# Powerboard.net
KiCad netlist of a schematic drawn in EAGLE
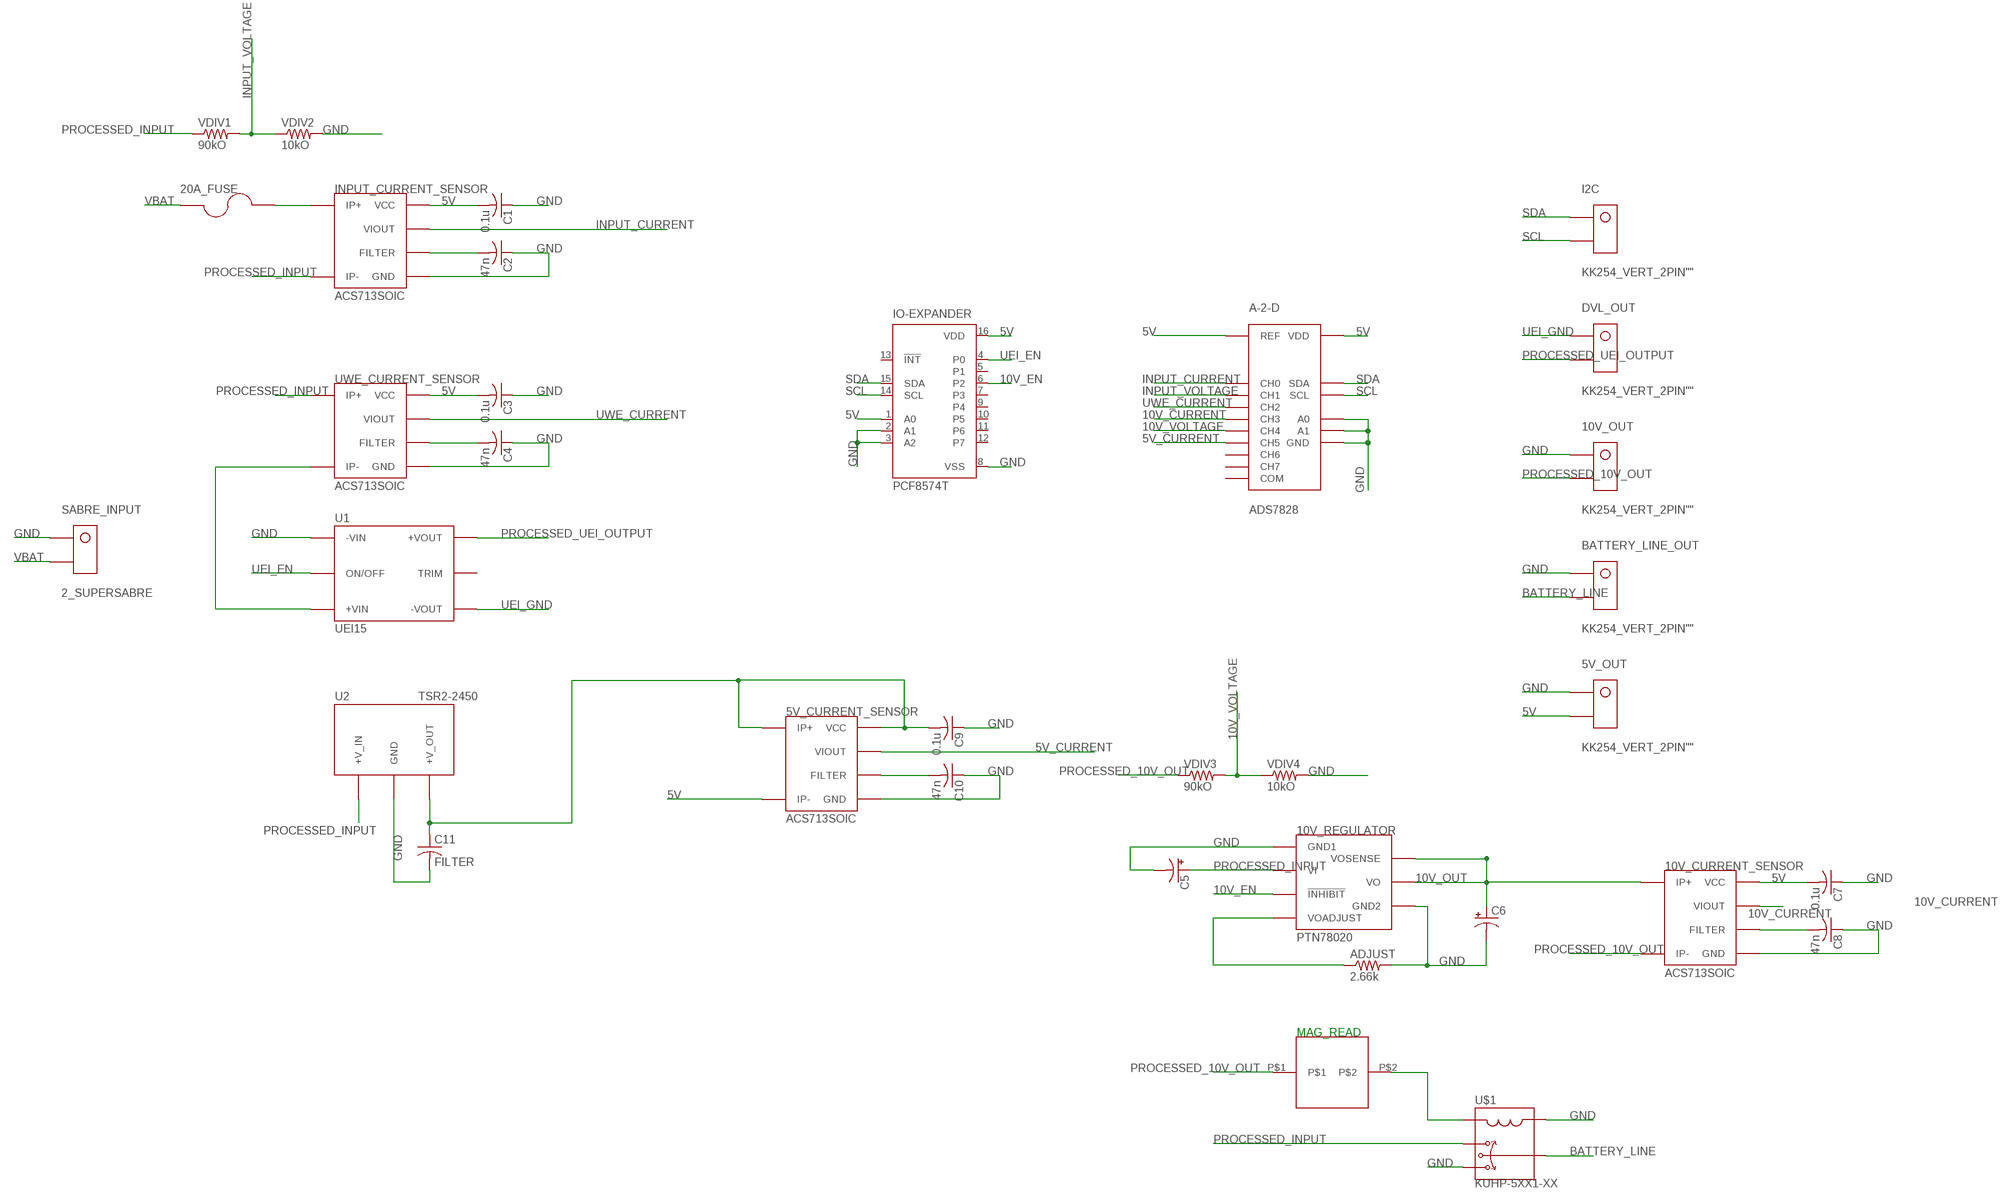
[diagram p0: schematic, sheet 1]

(export (version "E")
  (design (tool "Eeschema 10.0.6"))
  (components
    (comp (ref "5V_CURRENT_SENSOR")
      (value "ACS713SOIC")
      (footprint "eagle-import:ACS713-SOIC")
      (libsource (lib "eagle-import") (part "ACS713SOIC"))
    )
    (comp (ref "5V_OUT")
      (value "KK254_VERT_2PIN\"\"")
      (footprint "eagle-import:KK254_VERT_2PIN")
      (libsource (lib "eagle-import") (part "KK254_VERT_2PIN{dblquote}{dblquote}"))
    )
    (comp (ref "10V_CURRENT_SENSOR")
      (value "ACS713SOIC")
      (footprint "eagle-import:ACS713-SOIC")
      (libsource (lib "eagle-import") (part "ACS713SOIC"))
    )
    (comp (ref "10V_OUT")
      (value "KK254_VERT_2PIN\"\"")
      (footprint "eagle-import:KK254_VERT_2PIN")
      (libsource (lib "eagle-import") (part "KK254_VERT_2PIN{dblquote}{dblquote}"))
    )
    (comp (ref "10V_REGULATOR")
      (value "PTN78020")
      (footprint "eagle-import:PTN")
      (libsource (lib "eagle-import") (part "PTN78020"))
    )
    (comp (ref "20A_FUSE")
      (value "BOWED-1.25\"-FUSECLIPS")
      (footprint "eagle-import:1.25__FUSECLIPS")
      (libsource (lib "eagle-import") (part "BOWED-1.25{dblquote}-FUSECLIPS"))
    )
    (comp (ref "A-2-D")
      (value "ADS7828")
      (footprint "eagle-import:TSSOP16")
      (libsource (lib "eagle-import") (part "ADS7828"))
    )
    (comp (ref "ADJUST")
      (value "2.66k")
      (footprint "eagle-import:R0805")
      (libsource (lib "eagle-import") (part "R-US_R0805"))
    )
    (comp (ref "BATTERY_LINE_OUT")
      (value "KK254_VERT_2PIN\"\"")
      (footprint "eagle-import:KK254_VERT_2PIN")
      (libsource (lib "eagle-import") (part "KK254_VERT_2PIN{dblquote}{dblquote}"))
    )
    (comp (ref "C1")
      (value "0.1u")
      (footprint "eagle-import:C0805")
      (libsource (lib "eagle-import") (part "C-USC0805"))
    )
    (comp (ref "C2")
      (value "47n")
      (footprint "eagle-import:C0805")
      (libsource (lib "eagle-import") (part "C-USC0805"))
    )
    (comp (ref "C3")
      (value "0.1u")
      (footprint "eagle-import:C0805")
      (libsource (lib "eagle-import") (part "C-USC0805"))
    )
    (comp (ref "C4")
      (value "47n")
      (footprint "eagle-import:C0805")
      (libsource (lib "eagle-import") (part "C-USC0805"))
    )
    (comp (ref "C5")
      (value "CPOL-US")
      (footprint "eagle-import:PANASONIC_A_TYPE_M")
      (libsource (lib "eagle-import") (part "CPOL-US"))
    )
    (comp (ref "C6")
      (value "CPOL-US")
      (footprint "eagle-import:PANASONIC_A_TYPE_M")
      (libsource (lib "eagle-import") (part "CPOL-US"))
    )
    (comp (ref "C7")
      (value "0.1u")
      (footprint "eagle-import:C0805")
      (libsource (lib "eagle-import") (part "C-USC0805"))
    )
    (comp (ref "C8")
      (value "47n")
      (footprint "eagle-import:C0805")
      (libsource (lib "eagle-import") (part "C-USC0805"))
    )
    (comp (ref "C9")
      (value "0.1u")
      (footprint "eagle-import:C0805")
      (libsource (lib "eagle-import") (part "C-USC0805"))
    )
    (comp (ref "C10")
      (value "47n")
      (footprint "eagle-import:C0805")
      (libsource (lib "eagle-import") (part "C-USC0805"))
    )
    (comp (ref "C11")
      (value "FILTER")
      (footprint "eagle-import:C0805")
      (libsource (lib "eagle-import") (part "C-USC0805"))
    )
    (comp (ref "DVL_OUT")
      (value "KK254_VERT_2PIN\"\"")
      (footprint "eagle-import:KK254_VERT_2PIN")
      (libsource (lib "eagle-import") (part "KK254_VERT_2PIN{dblquote}{dblquote}"))
    )
    (comp (ref "I2C")
      (value "KK254_VERT_2PIN\"\"")
      (footprint "eagle-import:KK254_VERT_2PIN")
      (libsource (lib "eagle-import") (part "KK254_VERT_2PIN{dblquote}{dblquote}"))
    )
    (comp (ref "INPUT_CURRENT_SENSOR")
      (value "ACS713SOIC")
      (footprint "eagle-import:ACS713-SOIC")
      (libsource (lib "eagle-import") (part "ACS713SOIC"))
    )
    (comp (ref "IO-EXPANDER")
      (value "PCF8574T")
      (footprint "eagle-import:SO16W")
      (fields (field (name "MPN") "PCF8574T/3,512"))
      (libsource (lib "eagle-import") (part "PCF8574T"))
    )
    (comp (ref "MAGREAD")
      (value "HE151TR-ND")
      (footprint "eagle-import:HE151TR-ND")
      (libsource (lib "eagle-import") (part "HE151TR-ND"))
    )
    (comp (ref "SABRE_INPUT")
      (value "2_SUPERSABRE")
      (footprint "eagle-import:SUPERSABRE_2CIRCUIT")
      (libsource (lib "eagle-import") (part "2_SUPERSABRE"))
    )
    (comp (ref "U$1")
      (value "KUHP-5XX1-XX")
      (footprint "eagle-import:KUHP_6.35MM-QUICK-CONNECT")
      (libsource (lib "eagle-import") (part "KUHP-5XX1-XX"))
    )
    (comp (ref "U1")
      (value "UEI15")
      (footprint "eagle-import:UEI15")
      (libsource (lib "eagle-import") (part "UEI15"))
    )
    (comp (ref "U2")
      (value "TSR2-2450")
      (footprint "eagle-import:TSR2")
      (libsource (lib "eagle-import") (part "TSR2-2450"))
    )
    (comp (ref "UWE_CURRENT_SENSOR")
      (value "ACS713SOIC")
      (footprint "eagle-import:ACS713-SOIC")
      (libsource (lib "eagle-import") (part "ACS713SOIC"))
    )
    (comp (ref "VDIV1")
      (value "90kO")
      (footprint "eagle-import:R0805")
      (libsource (lib "eagle-import") (part "R-US_R0805"))
    )
    (comp (ref "VDIV2")
      (value "10kO")
      (footprint "eagle-import:R0805")
      (libsource (lib "eagle-import") (part "R-US_R0805"))
    )
    (comp (ref "VDIV3")
      (value "90kO")
      (footprint "eagle-import:R0805")
      (libsource (lib "eagle-import") (part "R-US_R0805"))
    )
    (comp (ref "VDIV4")
      (value "10kO")
      (footprint "eagle-import:R0805")
      (libsource (lib "eagle-import") (part "R-US_R0805"))
    )
  )
  (nets
    (net (code "1") (name "/5V") (class "Default")
      (node (ref "10V_CURRENT_SENSOR") (pin "P$8") (pinfunction "VCC_P$8") (pintype "bidirectional"))
      (node (ref "5V_CURRENT_SENSOR") (pin "P$3") (pinfunction "IP-_P$3") (pintype "bidirectional"))
      (node (ref "5V_CURRENT_SENSOR") (pin "P$4") (pinfunction "IP-_P$4") (pintype "bidirectional"))
      (node (ref "5V_OUT") (pin "P$2") (pinfunction "P$2_P$2") (pintype "bidirectional"))
      (node (ref "A-2-D") (pin "10") (pinfunction "REF_10") (pintype "bidirectional"))
      (node (ref "A-2-D") (pin "16") (pinfunction "VDD_16") (pintype "bidirectional"))
      (node (ref "C1") (pin "2") (pinfunction "2_2") (pintype "passive"))
      (node (ref "C3") (pin "2") (pinfunction "2_2") (pintype "passive"))
      (node (ref "C7") (pin "2") (pinfunction "2_2") (pintype "passive"))
      (node (ref "INPUT_CURRENT_SENSOR") (pin "P$8") (pinfunction "VCC_P$8") (pintype "bidirectional"))
      (node (ref "IO-EXPANDER") (pin "1") (pinfunction "A0_1") (pintype "input"))
      (node (ref "IO-EXPANDER") (pin "16") (pinfunction "VDD_16") (pintype "power_in"))
      (node (ref "UWE_CURRENT_SENSOR") (pin "P$8") (pinfunction "VCC_P$8") (pintype "bidirectional"))
    )
    (net (code "2") (name "/5V_CURRENT") (class "Default")
      (node (ref "5V_CURRENT_SENSOR") (pin "P$7") (pinfunction "VIOUT_P$7") (pintype "bidirectional"))
      (node (ref "A-2-D") (pin "6") (pinfunction "CH5_6") (pintype "bidirectional"))
    )
    (net (code "3") (name "/10V_CURRENT") (class "Default")
      (node (ref "10V_CURRENT_SENSOR") (pin "P$7") (pinfunction "VIOUT_P$7") (pintype "bidirectional"))
      (node (ref "A-2-D") (pin "4") (pinfunction "CH3_4") (pintype "bidirectional"))
    )
    (net (code "4") (name "/10V_EN") (class "Default")
      (node (ref "10V_REGULATOR") (pin "INHIBIT") (pinfunction "~{INHIBIT}_INHIBIT") (pintype "bidirectional"))
      (node (ref "IO-EXPANDER") (pin "6") (pinfunction "P2_6") (pintype "bidirectional"))
    )
    (net (code "5") (name "/10V_OUT") (class "Default")
      (node (ref "10V_CURRENT_SENSOR") (pin "P$1") (pinfunction "IP+_P$1") (pintype "bidirectional"))
      (node (ref "10V_CURRENT_SENSOR") (pin "P$2") (pinfunction "IP+_P$2") (pintype "bidirectional"))
      (node (ref "10V_REGULATOR") (pin "SENSE") (pinfunction "VOSENSE_SENSE") (pintype "bidirectional"))
      (node (ref "10V_REGULATOR") (pin "VOUT") (pinfunction "VO_VOUT") (pintype "bidirectional"))
      (node (ref "C6") (pin "+") (pinfunction "+_+") (pintype "passive"))
    )
    (net (code "6") (name "/10V_VOLTAGE") (class "Default")
      (node (ref "A-2-D") (pin "5") (pinfunction "CH4_5") (pintype "bidirectional"))
      (node (ref "VDIV3") (pin "2") (pinfunction "2_2") (pintype "passive"))
      (node (ref "VDIV4") (pin "1") (pinfunction "1_1") (pintype "passive"))
    )
    (net (code "7") (name "/BATTERY_LINE") (class "Default")
      (node (ref "BATTERY_LINE_OUT") (pin "P$2") (pinfunction "P$2_P$2") (pintype "bidirectional"))
      (node (ref "U$1") (pin "7A") (pinfunction "7_7A") (pintype "bidirectional"))
      (node (ref "U$1") (pin "7B") (pinfunction "7_7B") (pintype "bidirectional"))
    )
    (net (code "8") (name "/GND") (class "Default")
      (node (ref "10V_CURRENT_SENSOR") (pin "P$5") (pinfunction "GND_P$5") (pintype "bidirectional"))
      (node (ref "10V_OUT") (pin "P$1") (pinfunction "P$1_P$1") (pintype "bidirectional"))
      (node (ref "10V_REGULATOR") (pin "GND1") (pinfunction "GND1_GND1") (pintype "bidirectional"))
      (node (ref "10V_REGULATOR") (pin "GND2") (pinfunction "GND2_GND2") (pintype "bidirectional"))
      (node (ref "5V_CURRENT_SENSOR") (pin "P$5") (pinfunction "GND_P$5") (pintype "bidirectional"))
      (node (ref "5V_OUT") (pin "P$1") (pinfunction "P$1_P$1") (pintype "bidirectional"))
      (node (ref "A-2-D") (pin "12") (pinfunction "A0_12") (pintype "bidirectional"))
      (node (ref "A-2-D") (pin "13") (pinfunction "A1_13") (pintype "bidirectional"))
      (node (ref "A-2-D") (pin "9") (pinfunction "GND_9") (pintype "bidirectional"))
      (node (ref "ADJUST") (pin "2") (pinfunction "2_2") (pintype "passive"))
      (node (ref "BATTERY_LINE_OUT") (pin "P$1") (pinfunction "P$1_P$1") (pintype "bidirectional"))
      (node (ref "C1") (pin "1") (pinfunction "1_1") (pintype "passive"))
      (node (ref "C10") (pin "1") (pinfunction "1_1") (pintype "passive"))
      (node (ref "C11") (pin "2") (pinfunction "2_2") (pintype "passive"))
      (node (ref "C2") (pin "1") (pinfunction "1_1") (pintype "passive"))
      (node (ref "C3") (pin "1") (pinfunction "1_1") (pintype "passive"))
      (node (ref "C4") (pin "1") (pinfunction "1_1") (pintype "passive"))
      (node (ref "C5") (pin "-") (pinfunction "-_-") (pintype "passive"))
      (node (ref "C6") (pin "-") (pinfunction "-_-") (pintype "passive"))
      (node (ref "C7") (pin "1") (pinfunction "1_1") (pintype "passive"))
      (node (ref "C8") (pin "1") (pinfunction "1_1") (pintype "passive"))
      (node (ref "C9") (pin "1") (pinfunction "1_1") (pintype "passive"))
      (node (ref "INPUT_CURRENT_SENSOR") (pin "P$5") (pinfunction "GND_P$5") (pintype "bidirectional"))
      (node (ref "IO-EXPANDER") (pin "2") (pinfunction "A1_2") (pintype "input"))
      (node (ref "IO-EXPANDER") (pin "3") (pinfunction "A2_3") (pintype "input"))
      (node (ref "IO-EXPANDER") (pin "8") (pinfunction "VSS_8") (pintype "power_in"))
      (node (ref "SABRE_INPUT") (pin "P$1") (pinfunction "P$1_P$1") (pintype "bidirectional"))
      (node (ref "U$1") (pin "5A") (pinfunction "5_5A") (pintype "bidirectional"))
      (node (ref "U$1") (pin "5B") (pinfunction "5_5B") (pintype "bidirectional"))
      (node (ref "U$1") (pin "AA") (pinfunction "A_AA") (pintype "bidirectional"))
      (node (ref "U$1") (pin "AB") (pinfunction "A_AB") (pintype "bidirectional"))
      (node (ref "U1") (pin "-VIN") (pinfunction "-VIN_-VIN") (pintype "power_in"))
      (node (ref "U2") (pin "2") (pinfunction "GND_2") (pintype "power_in"))
      (node (ref "UWE_CURRENT_SENSOR") (pin "P$5") (pinfunction "GND_P$5") (pintype "bidirectional"))
      (node (ref "VDIV2") (pin "2") (pinfunction "2_2") (pintype "passive"))
      (node (ref "VDIV4") (pin "2") (pinfunction "2_2") (pintype "passive"))
    )
    (net (code "9") (name "/INPUT_CURRENT") (class "Default")
      (node (ref "A-2-D") (pin "1") (pinfunction "CH0_1") (pintype "bidirectional"))
      (node (ref "INPUT_CURRENT_SENSOR") (pin "P$7") (pinfunction "VIOUT_P$7") (pintype "bidirectional"))
    )
    (net (code "10") (name "/INPUT_VOLTAGE") (class "Default")
      (node (ref "A-2-D") (pin "2") (pinfunction "CH1_2") (pintype "bidirectional"))
      (node (ref "VDIV1") (pin "2") (pinfunction "2_2") (pintype "passive"))
      (node (ref "VDIV2") (pin "1") (pinfunction "1_1") (pintype "passive"))
    )
    (net (code "11") (name "/PROCESSED_10V_OUT") (class "Default")
      (node (ref "10V_CURRENT_SENSOR") (pin "P$3") (pinfunction "IP-_P$3") (pintype "bidirectional"))
      (node (ref "10V_CURRENT_SENSOR") (pin "P$4") (pinfunction "IP-_P$4") (pintype "bidirectional"))
      (node (ref "10V_OUT") (pin "P$2") (pinfunction "P$2_P$2") (pintype "bidirectional"))
      (node (ref "MAGREAD") (pin "P$1") (pinfunction "P$1_P$1") (pintype "bidirectional"))
      (node (ref "VDIV3") (pin "1") (pinfunction "1_1") (pintype "passive"))
    )
    (net (code "12") (name "/PROCESSED_INPUT") (class "Default")
      (node (ref "10V_REGULATOR") (pin "VIN") (pinfunction "VI_VIN") (pintype "bidirectional"))
      (node (ref "C5") (pin "+") (pinfunction "+_+") (pintype "passive"))
      (node (ref "INPUT_CURRENT_SENSOR") (pin "P$3") (pinfunction "IP-_P$3") (pintype "bidirectional"))
      (node (ref "INPUT_CURRENT_SENSOR") (pin "P$4") (pinfunction "IP-_P$4") (pintype "bidirectional"))
      (node (ref "U$1") (pin "2A") (pinfunction "2_2A") (pintype "bidirectional"))
      (node (ref "U$1") (pin "2B") (pinfunction "2_2B") (pintype "bidirectional"))
      (node (ref "U2") (pin "1") (pinfunction "+V_IN_1") (pintype "power_in"))
      (node (ref "UWE_CURRENT_SENSOR") (pin "P$1") (pinfunction "IP+_P$1") (pintype "bidirectional"))
      (node (ref "UWE_CURRENT_SENSOR") (pin "P$2") (pinfunction "IP+_P$2") (pintype "bidirectional"))
      (node (ref "VDIV1") (pin "1") (pinfunction "1_1") (pintype "passive"))
    )
    (net (code "13") (name "/PROCESSED_UEI_OUTPUT") (class "Default")
      (node (ref "DVL_OUT") (pin "P$2") (pinfunction "P$2_P$2") (pintype "bidirectional"))
      (node (ref "U1") (pin "+VOUT") (pinfunction "+VOUT_+VOUT") (pintype "power_in"))
    )
    (net (code "14") (name "/SCL") (class "Default")
      (node (ref "A-2-D") (pin "14") (pinfunction "SCL_14") (pintype "bidirectional"))
      (node (ref "I2C") (pin "P$2") (pinfunction "P$2_P$2") (pintype "bidirectional"))
      (node (ref "IO-EXPANDER") (pin "14") (pinfunction "SCL_14") (pintype "input"))
    )
    (net (code "15") (name "/SDA") (class "Default")
      (node (ref "A-2-D") (pin "15") (pinfunction "SDA_15") (pintype "bidirectional"))
      (node (ref "I2C") (pin "P$1") (pinfunction "P$1_P$1") (pintype "bidirectional"))
      (node (ref "IO-EXPANDER") (pin "15") (pinfunction "SDA_15") (pintype "bidirectional"))
    )
    (net (code "16") (name "/UEI_EN") (class "Default")
      (node (ref "IO-EXPANDER") (pin "4") (pinfunction "P0_4") (pintype "bidirectional"))
      (node (ref "U1") (pin "ON/OFFCNTRL") (pinfunction "ON/OFF_ON/OFFCNTRL") (pintype "bidirectional"))
    )
    (net (code "17") (name "/UEI_GND") (class "Default")
      (node (ref "DVL_OUT") (pin "P$1") (pinfunction "P$1_P$1") (pintype "bidirectional"))
      (node (ref "U1") (pin "-VOUT") (pinfunction "-VOUT_-VOUT") (pintype "power_in"))
    )
    (net (code "18") (name "/UWE_CURRENT") (class "Default")
      (node (ref "A-2-D") (pin "3") (pinfunction "CH2_3") (pintype "bidirectional"))
      (node (ref "UWE_CURRENT_SENSOR") (pin "P$7") (pinfunction "VIOUT_P$7") (pintype "bidirectional"))
    )
    (net (code "19") (name "/VBAT") (class "Default")
      (node (ref "20A_FUSE") (pin "P$1") (pinfunction "P$1_P$1") (pintype "bidirectional"))
      (node (ref "20A_FUSE") (pin "P$2") (pinfunction "P$1_P$2") (pintype "bidirectional"))
      (node (ref "SABRE_INPUT") (pin "P$2") (pinfunction "P$2_P$2") (pintype "bidirectional"))
    )
    (net (code "20") (name "Net-(5V_CURRENT_SENSOR-FILTER)") (class "Default")
      (node (ref "5V_CURRENT_SENSOR") (pin "P$6") (pinfunction "FILTER_P$6") (pintype "bidirectional"))
      (node (ref "C10") (pin "2") (pinfunction "2_2") (pintype "passive"))
    )
    (net (code "21") (name "Net-(5V_CURRENT_SENSOR-VCC)") (class "Default")
      (node (ref "5V_CURRENT_SENSOR") (pin "P$1") (pinfunction "IP+_P$1") (pintype "bidirectional"))
      (node (ref "5V_CURRENT_SENSOR") (pin "P$2") (pinfunction "IP+_P$2") (pintype "bidirectional"))
      (node (ref "5V_CURRENT_SENSOR") (pin "P$8") (pinfunction "VCC_P$8") (pintype "bidirectional"))
      (node (ref "C11") (pin "1") (pinfunction "1_1") (pintype "passive"))
      (node (ref "C9") (pin "2") (pinfunction "2_2") (pintype "passive"))
      (node (ref "U2") (pin "3") (pinfunction "+V_OUT_3") (pintype "power_in"))
    )
    (net (code "22") (name "Net-(10V_CURRENT_SENSOR-FILTER)") (class "Default")
      (node (ref "10V_CURRENT_SENSOR") (pin "P$6") (pinfunction "FILTER_P$6") (pintype "bidirectional"))
      (node (ref "C8") (pin "2") (pinfunction "2_2") (pintype "passive"))
    )
    (net (code "23") (name "Net-(10V_REGULATOR-VOADJUST)") (class "Default")
      (node (ref "10V_REGULATOR") (pin "ADJUST") (pinfunction "VOADJUST_ADJUST") (pintype "bidirectional"))
      (node (ref "ADJUST") (pin "1") (pinfunction "1_1") (pintype "passive"))
    )
    (net (code "24") (name "Net-(20A_FUSE-P$2-PadP$3)") (class "Default")
      (node (ref "20A_FUSE") (pin "P$3") (pinfunction "P$2_P$3") (pintype "bidirectional"))
      (node (ref "20A_FUSE") (pin "P$4") (pinfunction "P$2_P$4") (pintype "bidirectional"))
      (node (ref "INPUT_CURRENT_SENSOR") (pin "P$1") (pinfunction "IP+_P$1") (pintype "bidirectional"))
      (node (ref "INPUT_CURRENT_SENSOR") (pin "P$2") (pinfunction "IP+_P$2") (pintype "bidirectional"))
    )
    (net (code "25") (name "Net-(INPUT_CURRENT_SENSOR-FILTER)") (class "Default")
      (node (ref "C2") (pin "2") (pinfunction "2_2") (pintype "passive"))
      (node (ref "INPUT_CURRENT_SENSOR") (pin "P$6") (pinfunction "FILTER_P$6") (pintype "bidirectional"))
    )
    (net (code "26") (name "Net-(MAGREAD-PadP$2)") (class "Default")
      (node (ref "MAGREAD") (pin "P$2") (pinfunction "P$2_P$2") (pintype "bidirectional"))
      (node (ref "U$1") (pin "BA") (pinfunction "B_BA") (pintype "bidirectional"))
      (node (ref "U$1") (pin "BB") (pinfunction "B_BB") (pintype "bidirectional"))
    )
    (net (code "27") (name "Net-(U1-Pad+VIN)") (class "Default")
      (node (ref "U1") (pin "+VIN") (pinfunction "+VIN_+VIN") (pintype "power_in"))
      (node (ref "UWE_CURRENT_SENSOR") (pin "P$3") (pinfunction "IP-_P$3") (pintype "bidirectional"))
      (node (ref "UWE_CURRENT_SENSOR") (pin "P$4") (pinfunction "IP-_P$4") (pintype "bidirectional"))
    )
    (net (code "28") (name "Net-(UWE_CURRENT_SENSOR-FILTER)") (class "Default")
      (node (ref "C4") (pin "2") (pinfunction "2_2") (pintype "passive"))
      (node (ref "UWE_CURRENT_SENSOR") (pin "P$6") (pinfunction "FILTER_P$6") (pintype "bidirectional"))
    )
    (net (code "29") (name "unconnected-(A-2-D-CH6-Pad7)") (class "Default")
      (node (ref "A-2-D") (pin "7") (pinfunction "CH6_7") (pintype "bidirectional"))
    )
    (net (code "30") (name "unconnected-(A-2-D-CH7-Pad8)") (class "Default")
      (node (ref "A-2-D") (pin "8") (pinfunction "CH7_8") (pintype "bidirectional"))
    )
    (net (code "31") (name "unconnected-(A-2-D-COM-Pad11)") (class "Default")
      (node (ref "A-2-D") (pin "11") (pinfunction "COM_11") (pintype "bidirectional"))
    )
    (net (code "32") (name "unconnected-(IO-EXPANDER-P1-Pad5)") (class "Default")
      (node (ref "IO-EXPANDER") (pin "5") (pinfunction "P1_5") (pintype "bidirectional"))
    )
    (net (code "33") (name "unconnected-(IO-EXPANDER-P3-Pad7)") (class "Default")
      (node (ref "IO-EXPANDER") (pin "7") (pinfunction "P3_7") (pintype "bidirectional"))
    )
    (net (code "34") (name "unconnected-(IO-EXPANDER-P4-Pad9)") (class "Default")
      (node (ref "IO-EXPANDER") (pin "9") (pinfunction "P4_9") (pintype "bidirectional"))
    )
    (net (code "35") (name "unconnected-(IO-EXPANDER-P5-Pad10)") (class "Default")
      (node (ref "IO-EXPANDER") (pin "10") (pinfunction "P5_10") (pintype "bidirectional"))
    )
    (net (code "36") (name "unconnected-(IO-EXPANDER-P6-Pad11)") (class "Default")
      (node (ref "IO-EXPANDER") (pin "11") (pinfunction "P6_11") (pintype "bidirectional"))
    )
    (net (code "37") (name "unconnected-(IO-EXPANDER-P7-Pad12)") (class "Default")
      (node (ref "IO-EXPANDER") (pin "12") (pinfunction "P7_12") (pintype "bidirectional"))
    )
    (net (code "38") (name "unconnected-(IO-EXPANDER-~{INT}-Pad13)") (class "Default")
      (node (ref "IO-EXPANDER") (pin "13") (pinfunction "~{INT}_13") (pintype "output"))
    )
    (net (code "39") (name "unconnected-(U1-TRIM-PadOTPTTRIM)") (class "Default")
      (node (ref "U1") (pin "OTPTTRIM") (pinfunction "TRIM_OTPTTRIM") (pintype "bidirectional"))
    )
  )
)
